# 03_RFID.net
KiCad netlist of a schematic drawn in Altium Designer
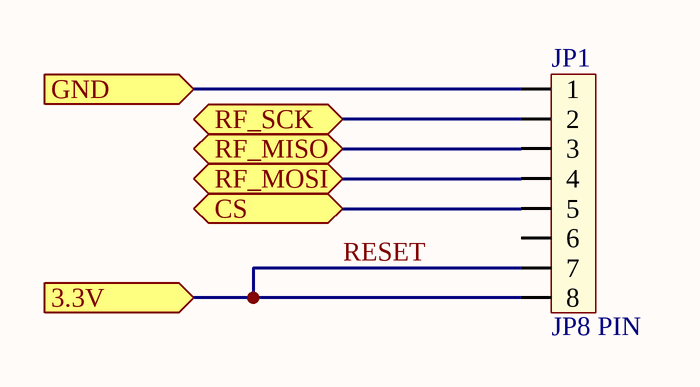
[diagram p0: 03_RFID.SchDoc]

(export (version "E")
  (design (tool "Eeschema 10.0.6"))
  (components
    (comp (ref "JP1") (value "JP8 PIN") (footprint "JP8") (libsource (lib "My Library") (part "JP8")))
  )
  (nets
    (net (code "1") (name "/CS") (class "Default")
      (node (ref "JP1") (pin "5") (pinfunction "5_5") (pintype "passive"))
    )
    (net (code "2") (name "/GND") (class "Default")
      (node (ref "JP1") (pin "1") (pinfunction "1_1") (pintype "passive"))
    )
    (net (code "3") (name "/RESET") (class "Default")
      (node (ref "JP1") (pin "7") (pinfunction "7_7") (pintype "passive"))
      (node (ref "JP1") (pin "8") (pinfunction "8_8") (pintype "passive"))
    )
    (net (code "4") (name "/RF_MISO") (class "Default")
      (node (ref "JP1") (pin "3") (pinfunction "3_3") (pintype "passive"))
    )
    (net (code "5") (name "/RF_MOSI") (class "Default")
      (node (ref "JP1") (pin "4") (pinfunction "4_4") (pintype "passive"))
    )
    (net (code "6") (name "/RF_SCK") (class "Default")
      (node (ref "JP1") (pin "2") (pinfunction "2_2") (pintype "passive"))
    )
    (net (code "7") (name "unconnected-(JP1-Pad6)") (class "Default")
      (node (ref "JP1") (pin "6") (pinfunction "6_6") (pintype "passive"))
    )
  )
)
